# POWER.net
KiCad netlist of a schematic drawn in Altium Designer
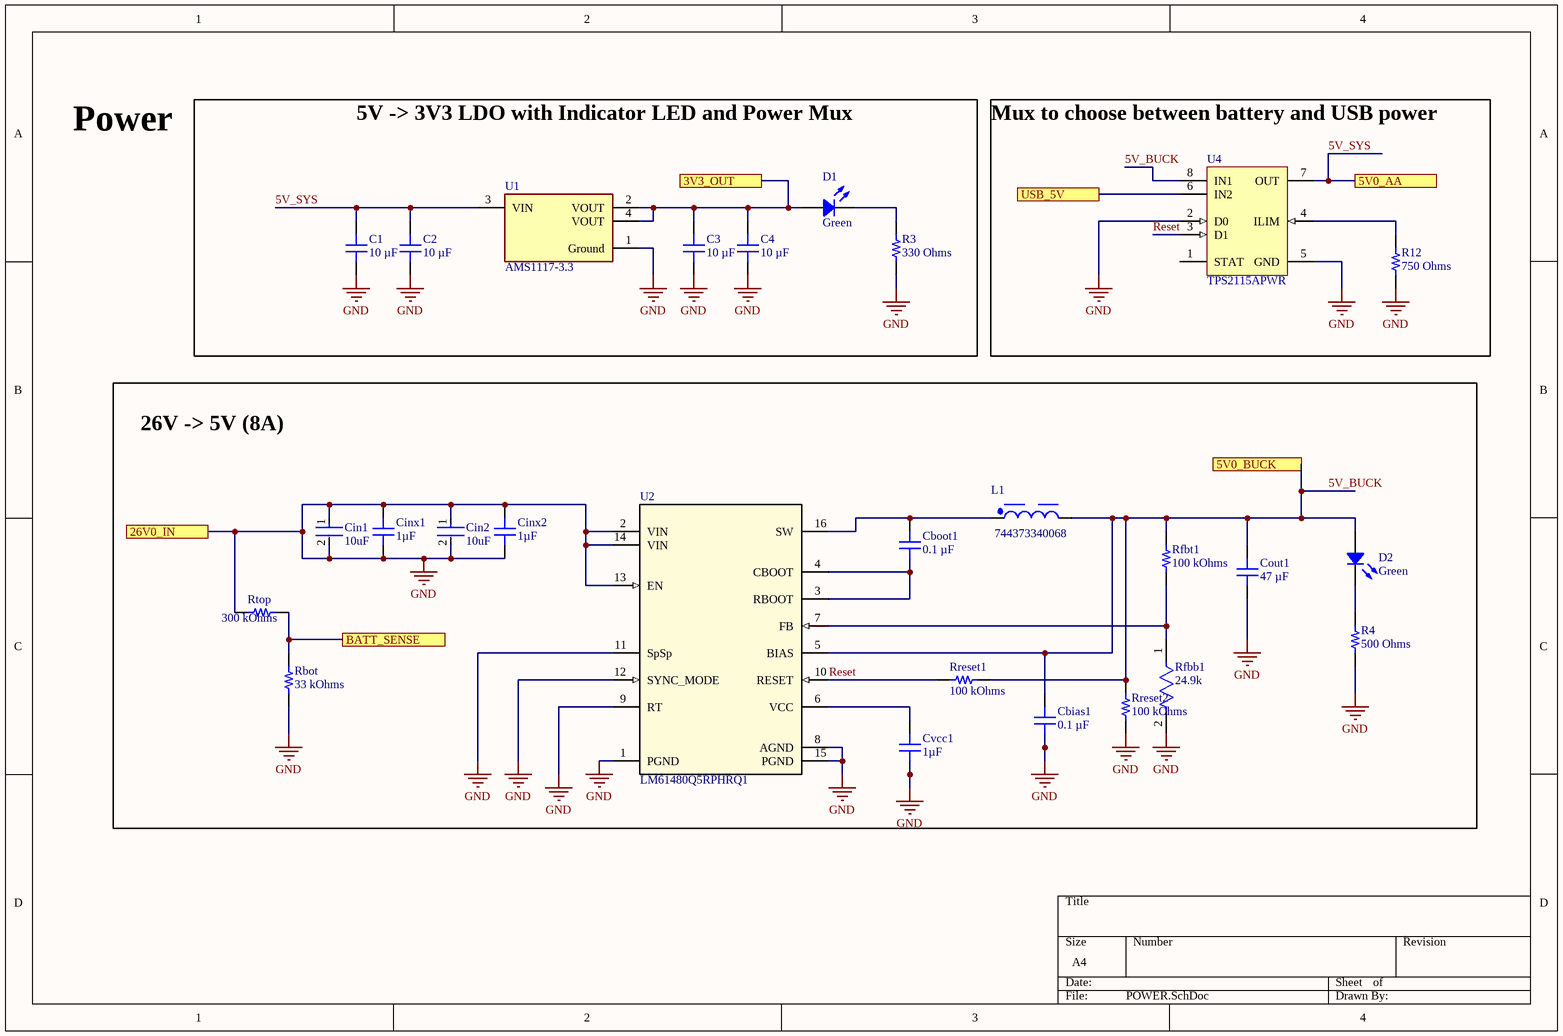
[diagram p0: POWER.SchDoc]

(export (version "E")
  (design (tool "Eeschema 10.0.6"))
  (components
    (comp (ref "C1")
      (value "10 µF")
      (footprint "CAP 0603_1608")
      (description "0603 X5R 10UF10% 16V")
      (fields (field (name "PART NUMBER") "CM105X5R106K16AT") (field (name "MANUFACTURER") "KYOCERA AVX"))
      (libsource (lib "Celestial Altium Library - altium_library") (part "Capacitor"))
    )
    (comp (ref "C2")
      (value "10 µF")
      (footprint "CAP 0603_1608")
      (description "0603 X5R 10UF10% 16V")
      (fields (field (name "PART NUMBER") "CM105X5R106K16AT") (field (name "MANUFACTURER") "KYOCERA AVX"))
      (libsource (lib "Celestial Altium Library - altium_library") (part "Capacitor"))
    )
    (comp (ref "C3")
      (value "10 µF")
      (footprint "CAP 0603_1608")
      (description "0603 X5R 10UF10% 16V")
      (fields (field (name "PART NUMBER") "CM105X5R106K16AT") (field (name "MANUFACTURER") "KYOCERA AVX"))
      (libsource (lib "Celestial Altium Library - altium_library") (part "Capacitor"))
    )
    (comp (ref "C4")
      (value "10 µF")
      (footprint "CAP 0603_1608")
      (description "0603 X5R 10UF10% 16V")
      (fields (field (name "PART NUMBER") "CM105X5R106K16AT") (field (name "MANUFACTURER") "KYOCERA AVX"))
      (libsource (lib "Celestial Altium Library - altium_library") (part "Capacitor"))
    )
    (comp (ref "Cbias1")
      (value "0.1 µF")
      (footprint "CAP 0603_1608")
      (description "CAP CER 0.1UF 50V X7R 0603")
      (fields
        (field (name "PART NUMBER") "C0603C104K5RAC7411")
        (field (name "CAPACITANCE") "0.1 µF")
        (field (name "MANUFACTURER") "KEMET")
      )
      (libsource (lib "Celestial Altium Library - altium_library") (part "Capacitor"))
    )
    (comp (ref "Cboot1")
      (value "0.1 µF")
      (footprint "CAP 0603_1608")
      (description "CAP CER 0.1UF 50V X7R 0603")
      (fields
        (field (name "PART NUMBER") "C0603C104K5RAC7411")
        (field (name "CAPACITANCE") "0.1 µF")
        (field (name "MANUFACTURER") "KEMET")
      )
      (libsource (lib "Celestial Altium Library - altium_library") (part "Capacitor"))
    )
    (comp (ref "Cin1")
      (value "10uF")
      (footprint "FP-GRT31C-0_2-IPC_A")
      (description "CAP CER 10UF 50V X5R 1206")
      (fields (field (name "TOLERANCE") "20%"))
      (libsource (lib "Altium Content Vault") (part "11868f565c42a9108669ba33697ecf6"))
    )
    (comp (ref "Cin2")
      (value "10uF")
      (footprint "FP-GRT31C-0_2-IPC_A")
      (description "CAP CER 10UF 50V X5R 1206")
      (fields (field (name "TOLERANCE") "20%"))
      (libsource (lib "Altium Content Vault") (part "11868f565c42a9108669ba33697ecf6"))
    )
    (comp (ref "Cinx1")
      (value "1µF")
      (footprint "CAP 0603_1608")
      (description "CAP CER 1UF 50V X5R 0603")
      (fields
        (field (name "PART NUMBER") "06035D105MAT2A")
        (field (name "CAPACITANCE") "1µF")
        (field (name "MANUFACTURER") "AVX Corporation")
      )
      (libsource (lib "Celestial Altium Library - altium_library") (part "Capacitor"))
    )
    (comp (ref "Cinx2")
      (value "1µF")
      (footprint "CAP 0603_1608")
      (description "CAP CER 1UF 50V X5R 0603")
      (fields
        (field (name "PART NUMBER") "06035D105MAT2A")
        (field (name "CAPACITANCE") "1µF")
        (field (name "MANUFACTURER") "AVX Corporation")
      )
      (libsource (lib "Celestial Altium Library - altium_library") (part "Capacitor"))
    )
    (comp (ref "Cout1")
      (value "47 µF")
      (footprint "CAP 0603_1608")
      (description "CAP CER 47UF 6.3V X5R 0603")
      (fields
        (field (name "PART NUMBER") "CL10A476MQ8QRNC")
        (field (name "CAPACITANCE") "47 µF")
        (field (name "MANUFACTURER") "Samsung Electro-Mechanics")
      )
      (libsource (lib "Celestial Altium Library - altium_library") (part "Capacitor"))
    )
    (comp (ref "Cvcc1")
      (value "1µF")
      (footprint "CAP 0603_1608")
      (description "CAP CER 1UF 50V X5R 0603")
      (fields
        (field (name "PART NUMBER") "06035D105MAT2A")
        (field (name "CAPACITANCE") "1µF")
        (field (name "MANUFACTURER") "AVX Corporation")
      )
      (libsource (lib "Celestial Altium Library - altium_library") (part "Capacitor"))
    )
    (comp (ref "D1")
      (value "Green")
      (footprint "LED 0603_1608 GREEN")
      (description "LED GREEN CLEAR 0603 SMD")
      (fields (field (name "PART NUMBER") "150060GS75003") (field (name "MANUFACTURER") "Würth Elektronik"))
      (libsource (lib "Celestial Altium Library - altium_library") (part "LED"))
    )
    (comp (ref "D2")
      (value "Green")
      (footprint "LED 0603_1608 GREEN")
      (description "LED GREEN CLEAR 0603 SMD")
      (fields (field (name "PART NUMBER") "150060GS75003") (field (name "MANUFACTURER") "Würth Elektronik"))
      (libsource (lib "Celestial Altium Library - altium_library") (part "LED"))
    )
    (comp (ref "L1")
      (value "744373340068")
      (footprint "WE-LHMI_5020")
      (description "We-lhmi Series, Shielded Wire-wound SMD Inductor 680 Nh +/-20% Wire-wound 6.8A I")
      (fields (field (name "TOLERANCE") "20%"))
      (libsource (lib "Altium Content Vault") (part "Inductor - 2"))
    )
    (comp (ref "R3")
      (value "330 Ohms")
      (footprint "RES 0603_1608")
      (description "RES 330 OHM 0.1% 1/8W 0603")
      (fields
        (field (name "PART NUMBER") "ERA-3VEB3300V")
        (field (name "MANUFACTURER") "Panasonic Electronic Components")
      )
      (libsource (lib "Celestial Altium Library - altium_library") (part "Resistor"))
    )
    (comp (ref "R4")
      (value "500 Ohms")
      (footprint "RES 1206_3216")
      (description "RES SMD 500 OHM 0.05% 0.4W 1206")
      (fields
        (field (name "PART NUMBER") "PLT1206Z5000AST5")
        (field (name "MANUFACTURER") "Vishay Thin Film")
      )
      (libsource (lib "Celestial Altium Library - altium_library") (part "Resistor"))
    )
    (comp (ref "R12")
      (value "750 Ohms")
      (footprint "RES 0603_1608")
      (description "RES SMD 750 OHM 1% 1/16W 0603")
      (fields
        (field (name "PART NUMBER") "CPF0603F750RC1")
        (field (name "MANUFACTURER") "TE Connectivity Passive Product")
      )
      (libsource (lib "Celestial Altium Library - altium_library") (part "Resistor"))
    )
    (comp (ref "Rbot")
      (value "33 kOhms")
      (footprint "YAGEO RES 0603_1608")
      (description "RES SMD 33K OHM 1% 1/10W 0603")
      (fields (field (name "PART NUMBER") "RT0603FRE0733KL") (field (name "MANUFACTURER") "Yageo"))
      (libsource (lib "Celestial Altium Library - altium_library") (part "Resistor"))
    )
    (comp (ref "Rfbb1")
      (value "24.9k")
      (footprint "FP-TFCR0603-IPC_A")
      (description "RES Thin Film,  24.9kΩ, 1%, 0.1W, 50ppm/°C, 0603")
      (libsource (lib "Altium Content Vault") (part "1029c3af85768c4190bb7ad29bc67b5"))
    )
    (comp (ref "Rfbt1")
      (value "100 kOhms")
      (footprint "RES 0603_1608")
      (description "RES 100K OHM 0.1% 1/16W 0603")
      (fields
        (field (name "PART NUMBER") "RNCS0603BKE100K")
        (field (name "MANUFACTURER") "Stackpole Electronics Inc")
      )
      (libsource (lib "Celestial Altium Library - altium_library") (part "Resistor"))
    )
    (comp (ref "Rreset1")
      (value "100 kOhms")
      (footprint "RES 0603_1608")
      (description "RES 100K OHM 0.1% 1/16W 0603")
      (fields
        (field (name "PART NUMBER") "RNCS0603BKE100K")
        (field (name "MANUFACTURER") "Stackpole Electronics Inc")
      )
      (libsource (lib "Celestial Altium Library - altium_library") (part "Resistor"))
    )
    (comp (ref "Rreset2")
      (value "100 kOhms")
      (footprint "RES 0603_1608")
      (description "RES 100K OHM 0.1% 1/16W 0603")
      (fields
        (field (name "PART NUMBER") "RNCS0603BKE100K")
        (field (name "MANUFACTURER") "Stackpole Electronics Inc")
      )
      (libsource (lib "Celestial Altium Library - altium_library") (part "Resistor"))
    )
    (comp (ref "Rtop")
      (value "300 kOhms")
      (footprint "YAGEO RES 0603_1608")
      (description "RES 300K OHM 1% 1/10W 0603")
      (fields (field (name "PART NUMBER") "RC0603FR-07300KL") (field (name "MANUFACTURER") "Yageo"))
      (libsource (lib "Celestial Altium Library - altium_library") (part "Resistor"))
    )
    (comp (ref "U1")
      (value "AMS1117-3.3")
      (footprint "FP-AMS1117-IPC_C")
      (description "LDO Voltage Regulators 1A, 3.3V")
      (fields
        (field (name "OCTOPART") "https://octopart.com/ams1117-3.3-advanced+monolithic+systems-25899300")
        (field (name "MANUFACTURER") "Advanced Monolithic Systems")
      )
      (libsource (lib "Altium Content Vault") (part "8bdbb5f8e77002000e30dd2845d0354"))
    )
    (comp (ref "U2")
      (value "LM61480Q5RPHRQ1")
      (footprint "RPH0016A")
      (description "Automotive 8A buck converter optimized for power density and low EMI 16-VQFN-HR -40 to 150")
      (fields (field (name "COPYRIGHT") "Copyright (C) 2025 Ultra Librarian. All rights reserved."))
      (libsource (lib "LM61480Q5RPHRQ1") (part "LM61480Q5RPHRQ1"))
    )
    (comp (ref "U4")
      (value "TPS2115APWR")
      (footprint "PW0008A_N")
      (fields (field (name "MANUFACTURER") "Texas Instruments"))
      (libsource (lib "Altium Content Vault") (part "TI-TPS2115APW8"))
    )
  )
  (nets
    (net (code "1") (name "/3V3_OUT") (class "Default")
      (node (ref "C3") (pin "2") (pinfunction "2_2") (pintype "passive"))
      (node (ref "C4") (pin "2") (pinfunction "2_2") (pintype "passive"))
      (node (ref "D1") (pin "1") (pinfunction "1_1") (pintype "passive"))
      (node (ref "U1") (pin "2") (pinfunction "VOUT_2") (pintype "passive"))
      (node (ref "U1") (pin "4") (pinfunction "VOUT_4") (pintype "passive"))
    )
    (net (code "2") (name "/5V_BUCK") (class "Default")
      (node (ref "Cbias1") (pin "1") (pinfunction "1_1") (pintype "passive"))
      (node (ref "Cout1") (pin "1") (pinfunction "1_1") (pintype "passive"))
      (node (ref "D2") (pin "1") (pinfunction "1_1") (pintype "passive"))
      (node (ref "L1") (pin "2") (pinfunction "2_2") (pintype "passive"))
      (node (ref "Rfbt1") (pin "1") (pinfunction "1_1") (pintype "passive"))
      (node (ref "Rreset1") (pin "2") (pinfunction "2_2") (pintype "passive"))
      (node (ref "Rreset2") (pin "1") (pinfunction "1_1") (pintype "passive"))
      (node (ref "U2") (pin "5") (pinfunction "BIAS_5") (pintype "passive"))
      (node (ref "U4") (pin "8") (pinfunction "IN1_8") (pintype "power_in"))
    )
    (net (code "3") (name "/5V_SYS") (class "Default")
      (node (ref "C1") (pin "2") (pinfunction "2_2") (pintype "passive"))
      (node (ref "C2") (pin "2") (pinfunction "2_2") (pintype "passive"))
      (node (ref "U1") (pin "3") (pinfunction "VIN_3") (pintype "power_in"))
      (node (ref "U4") (pin "7") (pinfunction "OUT_7") (pintype "power_in"))
    )
    (net (code "4") (name "/BATT_SENSE") (class "Default")
      (node (ref "Rbot") (pin "1") (pinfunction "1_1") (pintype "passive"))
      (node (ref "Rtop") (pin "2") (pinfunction "2_2") (pintype "passive"))
    )
    (net (code "5") (name "/Reset") (class "Default")
      (node (ref "Rreset1") (pin "1") (pinfunction "1_1") (pintype "passive"))
      (node (ref "U2") (pin "10") (pinfunction "RESET_10") (pintype "input"))
      (node (ref "U4") (pin "3") (pinfunction "D1_3") (pintype "input"))
    )
    (net (code "6") (name "/USB_5V") (class "Default")
      (node (ref "U4") (pin "6") (pinfunction "IN2_6") (pintype "power_in"))
    )
    (net (code "7") (name "GND") (class "Default")
      (node (ref "C1") (pin "1") (pinfunction "1_1") (pintype "passive"))
      (node (ref "C2") (pin "1") (pinfunction "1_1") (pintype "passive"))
      (node (ref "C3") (pin "1") (pinfunction "1_1") (pintype "passive"))
      (node (ref "C4") (pin "1") (pinfunction "1_1") (pintype "passive"))
      (node (ref "Cbias1") (pin "2") (pinfunction "2_2") (pintype "passive"))
      (node (ref "Cin1") (pin "1") (pinfunction "1_1") (pintype "passive"))
      (node (ref "Cin1") (pin "2") (pinfunction "2_2") (pintype "passive"))
      (node (ref "Cin2") (pin "1") (pinfunction "1_1") (pintype "passive"))
      (node (ref "Cin2") (pin "2") (pinfunction "2_2") (pintype "passive"))
      (node (ref "Cinx1") (pin "1") (pinfunction "1_1") (pintype "passive"))
      (node (ref "Cinx1") (pin "2") (pinfunction "2_2") (pintype "passive"))
      (node (ref "Cinx2") (pin "1") (pinfunction "1_1") (pintype "passive"))
      (node (ref "Cinx2") (pin "2") (pinfunction "2_2") (pintype "passive"))
      (node (ref "Cout1") (pin "2") (pinfunction "2_2") (pintype "passive"))
      (node (ref "Cvcc1") (pin "2") (pinfunction "2_2") (pintype "passive"))
      (node (ref "R12") (pin "2") (pinfunction "2_2") (pintype "passive"))
      (node (ref "R3") (pin "1") (pinfunction "1_1") (pintype "passive"))
      (node (ref "R4") (pin "2") (pinfunction "2_2") (pintype "passive"))
      (node (ref "Rbot") (pin "2") (pinfunction "2_2") (pintype "passive"))
      (node (ref "Rfbb1") (pin "2") (pinfunction "2_2") (pintype "passive"))
      (node (ref "Rreset2") (pin "2") (pinfunction "2_2") (pintype "passive"))
      (node (ref "Rtop") (pin "1") (pinfunction "1_1") (pintype "passive"))
      (node (ref "U1") (pin "1") (pinfunction "Ground_1") (pintype "power_in"))
      (node (ref "U2") (pin "1") (pinfunction "PGND_1") (pintype "power_in"))
      (node (ref "U2") (pin "11") (pinfunction "SpSp_11") (pintype "passive"))
      (node (ref "U2") (pin "12") (pinfunction "SYNC_MODE_12") (pintype "input"))
      (node (ref "U2") (pin "13") (pinfunction "EN_13") (pintype "input"))
      (node (ref "U2") (pin "14") (pinfunction "VIN_14") (pintype "power_in"))
      (node (ref "U2") (pin "15") (pinfunction "PGND_15") (pintype "power_in"))
      (node (ref "U2") (pin "2") (pinfunction "VIN_2") (pintype "power_in"))
      (node (ref "U2") (pin "8") (pinfunction "AGND_8") (pintype "power_in"))
      (node (ref "U2") (pin "9") (pinfunction "RT_9") (pintype "passive"))
      (node (ref "U4") (pin "2") (pinfunction "D0_2") (pintype "input"))
      (node (ref "U4") (pin "5") (pinfunction "GND_5") (pintype "power_in"))
    )
    (net (code "8") (name "Net-(D1-Pad2)") (class "Default")
      (node (ref "D1") (pin "2") (pinfunction "2_2") (pintype "passive"))
      (node (ref "R3") (pin "2") (pinfunction "2_2") (pintype "passive"))
    )
    (net (code "9") (name "Net-(D2-Pad2)") (class "Default")
      (node (ref "D2") (pin "2") (pinfunction "2_2") (pintype "passive"))
      (node (ref "R4") (pin "1") (pinfunction "1_1") (pintype "passive"))
    )
    (net (code "10") (name "Net-(U2-CBOOT)") (class "Default")
      (node (ref "Cboot1") (pin "2") (pinfunction "2_2") (pintype "passive"))
      (node (ref "U2") (pin "3") (pinfunction "RBOOT_3") (pintype "passive"))
      (node (ref "U2") (pin "4") (pinfunction "CBOOT_4") (pintype "passive"))
    )
    (net (code "11") (name "Net-(U2-FB)") (class "Default")
      (node (ref "Rfbb1") (pin "1") (pinfunction "1_1") (pintype "passive"))
      (node (ref "Rfbt1") (pin "2") (pinfunction "2_2") (pintype "passive"))
      (node (ref "U2") (pin "7") (pinfunction "FB_7") (pintype "input"))
    )
    (net (code "12") (name "Net-(U2-SW)") (class "Default")
      (node (ref "Cboot1") (pin "1") (pinfunction "1_1") (pintype "passive"))
      (node (ref "L1") (pin "1") (pinfunction "1_1") (pintype "passive"))
      (node (ref "U2") (pin "16") (pinfunction "SW_16") (pintype "power_in"))
    )
    (net (code "13") (name "Net-(U2-VCC)") (class "Default")
      (node (ref "Cvcc1") (pin "1") (pinfunction "1_1") (pintype "passive"))
      (node (ref "U2") (pin "6") (pinfunction "VCC_6") (pintype "power_in"))
    )
    (net (code "14") (name "Net-(U4-ILIM)") (class "Default")
      (node (ref "R12") (pin "1") (pinfunction "1_1") (pintype "passive"))
      (node (ref "U4") (pin "4") (pinfunction "ILIM_4") (pintype "input"))
    )
    (net (code "15") (name "unconnected-(U4-STAT-Pad1)") (class "Default")
      (node (ref "U4") (pin "1") (pinfunction "STAT_1") (pintype "tri_state"))
    )
  )
)
